# guitar_tuner.net
KiCad netlist of a schematic drawn in EAGLE
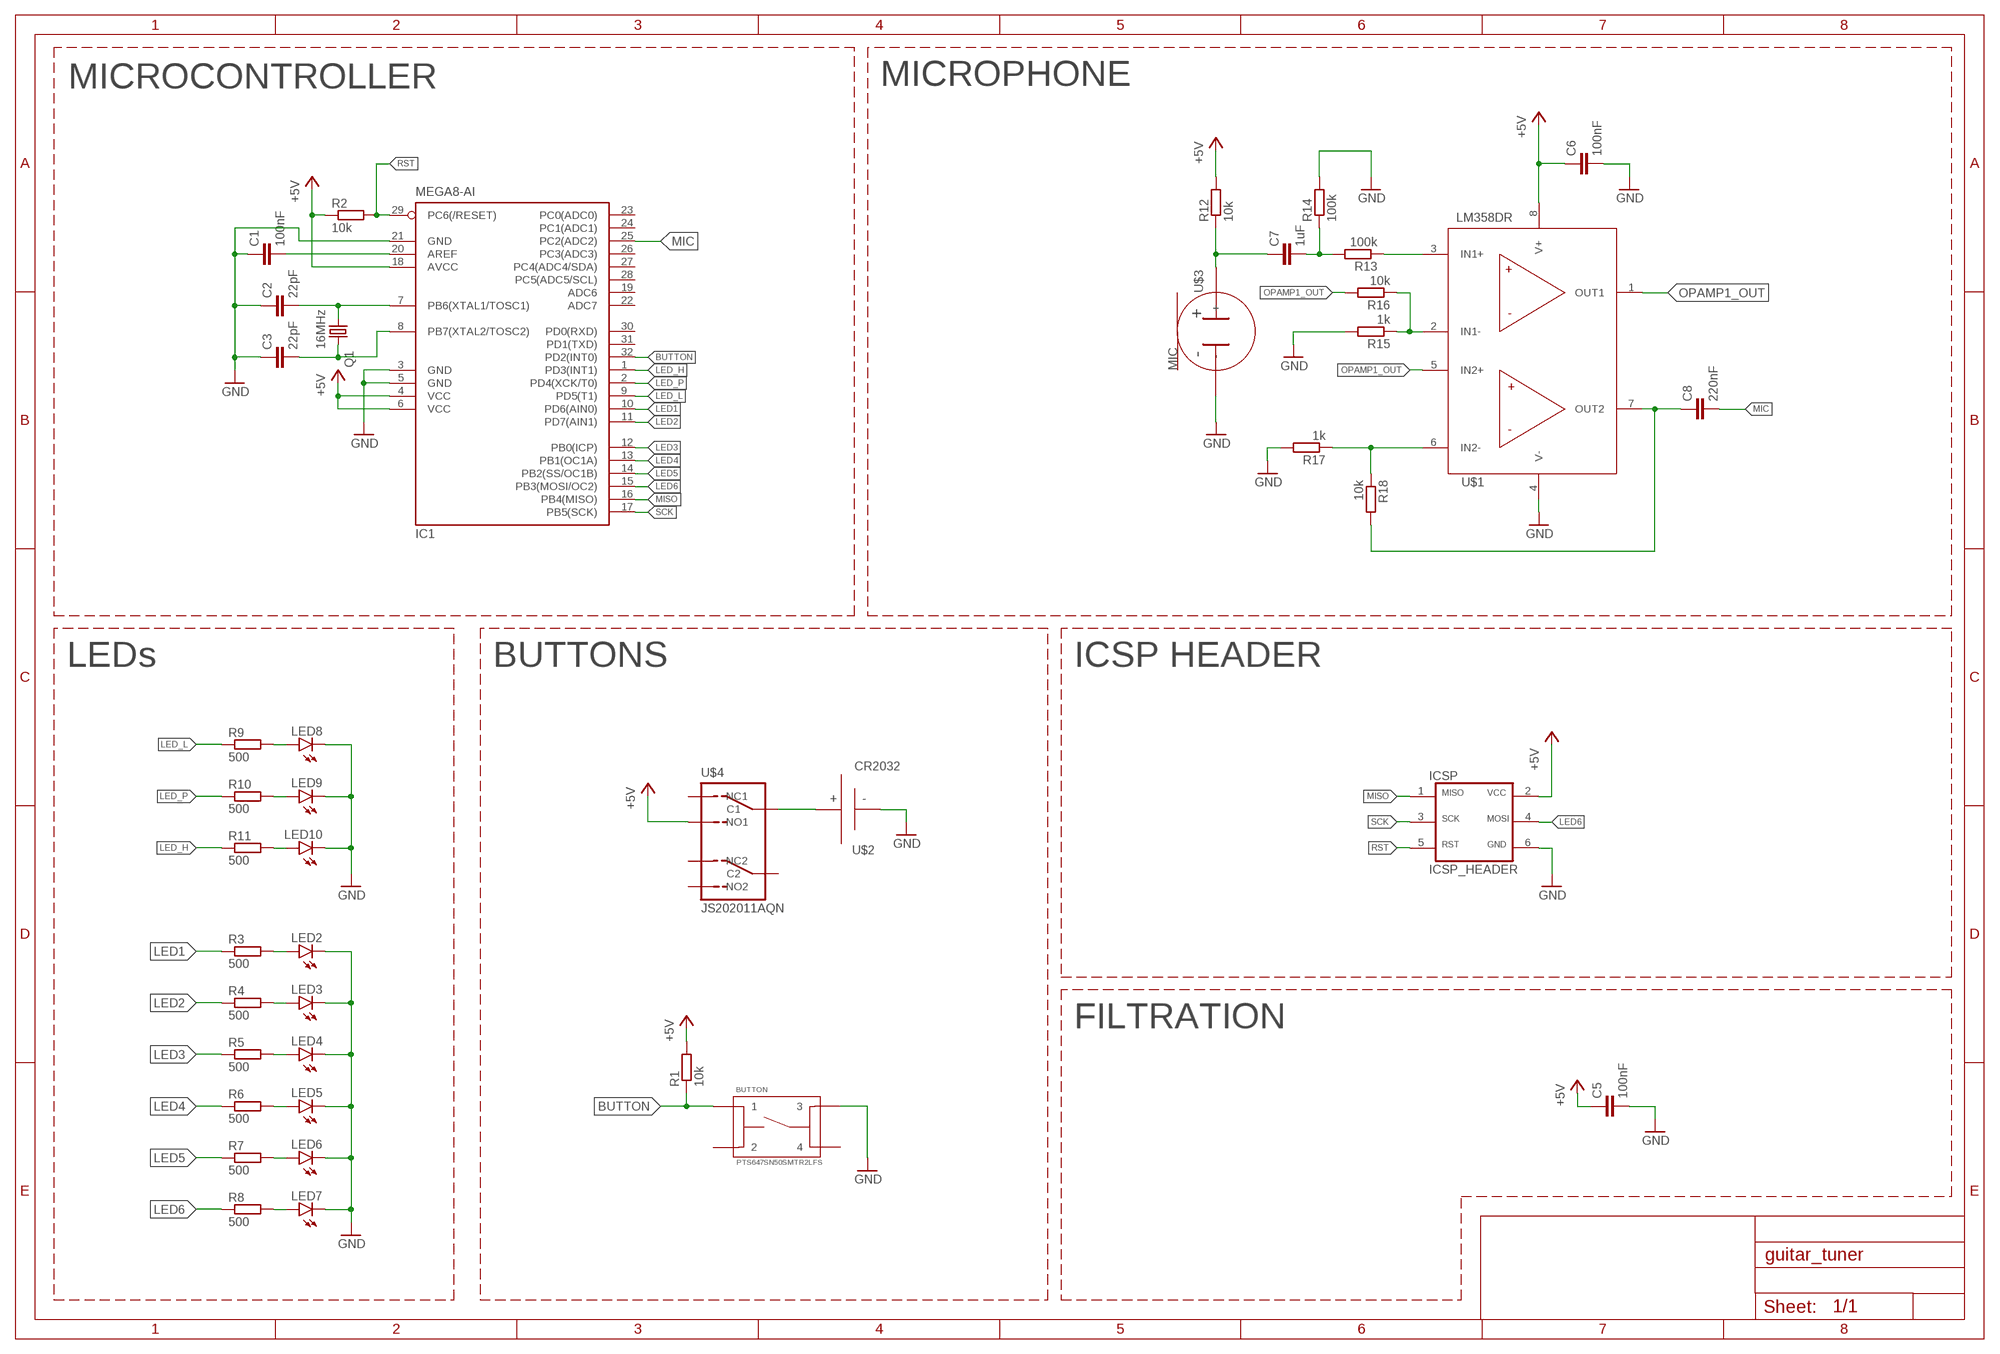
[diagram p0: schematic, sheet 1]

(export (version "E")
  (design (tool "Eeschema 10.0.6"))
  (components
    (comp (ref "BUTTON")
      (value "PTS647SN50SMTR2LFS")
      (footprint "eagle-import:PTS647_SMD_TACTSWITCH")
      (libsource (lib "eagle-import") (part "PTS647SN50SMTR2LFS"))
    )
    (comp (ref "C1")
      (value "100nF")
      (footprint "eagle-import:C0603")
      (libsource (lib "eagle-import") (part "C-EUC0603"))
    )
    (comp (ref "C2")
      (value "22pF")
      (footprint "eagle-import:C0603")
      (libsource (lib "eagle-import") (part "C-EUC0603"))
    )
    (comp (ref "C3")
      (value "22pF")
      (footprint "eagle-import:C0603")
      (libsource (lib "eagle-import") (part "C-EUC0603"))
    )
    (comp (ref "C5")
      (value "100nF")
      (footprint "eagle-import:C0603")
      (libsource (lib "eagle-import") (part "C-EUC0603"))
    )
    (comp (ref "C6")
      (value "100nF")
      (footprint "eagle-import:C0603")
      (libsource (lib "eagle-import") (part "C-EUC0603"))
    )
    (comp (ref "C7")
      (value "1uF")
      (footprint "eagle-import:C0603")
      (libsource (lib "eagle-import") (part "C-EUC0603"))
    )
    (comp (ref "C8")
      (value "220nF")
      (footprint "eagle-import:C0603")
      (libsource (lib "eagle-import") (part "C-EUC0603"))
    )
    (comp (ref "IC1")
      (value "MEGA8-AI")
      (footprint "eagle-import:TQFP32-08")
      (fields (field (name "MPN") "ATMEGA8-16AU"))
      (libsource (lib "eagle-import") (part "MEGA8-AI"))
    )
    (comp (ref "LED2")
      (value "LEDCHIPLED_1206")
      (footprint "eagle-import:CHIPLED_1206")
      (libsource (lib "eagle-import") (part "LEDCHIPLED_1206"))
    )
    (comp (ref "LED3")
      (value "LEDCHIPLED_1206")
      (footprint "eagle-import:CHIPLED_1206")
      (libsource (lib "eagle-import") (part "LEDCHIPLED_1206"))
    )
    (comp (ref "LED4")
      (value "LEDCHIPLED_1206")
      (footprint "eagle-import:CHIPLED_1206")
      (libsource (lib "eagle-import") (part "LEDCHIPLED_1206"))
    )
    (comp (ref "LED5")
      (value "LEDCHIPLED_1206")
      (footprint "eagle-import:CHIPLED_1206")
      (libsource (lib "eagle-import") (part "LEDCHIPLED_1206"))
    )
    (comp (ref "LED6")
      (value "LEDCHIPLED_1206")
      (footprint "eagle-import:CHIPLED_1206")
      (libsource (lib "eagle-import") (part "LEDCHIPLED_1206"))
    )
    (comp (ref "LED7")
      (value "LEDCHIPLED_1206")
      (footprint "eagle-import:CHIPLED_1206")
      (libsource (lib "eagle-import") (part "LEDCHIPLED_1206"))
    )
    (comp (ref "LED8")
      (value "LEDCHIPLED_1206")
      (footprint "eagle-import:CHIPLED_1206")
      (libsource (lib "eagle-import") (part "LEDCHIPLED_1206"))
    )
    (comp (ref "LED9")
      (value "LEDCHIPLED_1206")
      (footprint "eagle-import:CHIPLED_1206")
      (libsource (lib "eagle-import") (part "LEDCHIPLED_1206"))
    )
    (comp (ref "LED10")
      (value "LEDCHIPLED_1206")
      (footprint "eagle-import:CHIPLED_1206")
      (libsource (lib "eagle-import") (part "LEDCHIPLED_1206"))
    )
    (comp (ref "Q1")
      (value "16MHz")
      (footprint "eagle-import:5.0X3.2_2")
      (libsource (lib "eagle-import") (part "KX-9B"))
    )
    (comp (ref "R1")
      (value "10k")
      (footprint "eagle-import:R0603")
      (libsource (lib "eagle-import") (part "R-EU_R0603"))
    )
    (comp (ref "R2")
      (value "10k")
      (footprint "eagle-import:R0603")
      (libsource (lib "eagle-import") (part "R-EU_R0603"))
    )
    (comp (ref "R3")
      (value "500")
      (footprint "eagle-import:R0603")
      (libsource (lib "eagle-import") (part "R-EU_R0603"))
    )
    (comp (ref "R4")
      (value "500")
      (footprint "eagle-import:R0603")
      (libsource (lib "eagle-import") (part "R-EU_R0603"))
    )
    (comp (ref "R5")
      (value "500")
      (footprint "eagle-import:R0603")
      (libsource (lib "eagle-import") (part "R-EU_R0603"))
    )
    (comp (ref "R6")
      (value "500")
      (footprint "eagle-import:R0603")
      (libsource (lib "eagle-import") (part "R-EU_R0603"))
    )
    (comp (ref "R7")
      (value "500")
      (footprint "eagle-import:R0603")
      (libsource (lib "eagle-import") (part "R-EU_R0603"))
    )
    (comp (ref "R8")
      (value "500")
      (footprint "eagle-import:R0603")
      (libsource (lib "eagle-import") (part "R-EU_R0603"))
    )
    (comp (ref "R9")
      (value "500")
      (footprint "eagle-import:R0603")
      (libsource (lib "eagle-import") (part "R-EU_R0603"))
    )
    (comp (ref "R10")
      (value "500")
      (footprint "eagle-import:R0603")
      (libsource (lib "eagle-import") (part "R-EU_R0603"))
    )
    (comp (ref "R11")
      (value "500")
      (footprint "eagle-import:R0603")
      (libsource (lib "eagle-import") (part "R-EU_R0603"))
    )
    (comp (ref "R12")
      (value "10k")
      (footprint "eagle-import:R0603")
      (libsource (lib "eagle-import") (part "R-EU_R0603"))
    )
    (comp (ref "R13")
      (value "100k")
      (footprint "eagle-import:R0603")
      (libsource (lib "eagle-import") (part "R-EU_R0603"))
    )
    (comp (ref "R14")
      (value "100k")
      (footprint "eagle-import:R0603")
      (libsource (lib "eagle-import") (part "R-EU_R0603"))
    )
    (comp (ref "R15")
      (value "1k")
      (footprint "eagle-import:R0603")
      (libsource (lib "eagle-import") (part "R-EU_R0603"))
    )
    (comp (ref "R16")
      (value "10k")
      (footprint "eagle-import:R0603")
      (libsource (lib "eagle-import") (part "R-EU_R0603"))
    )
    (comp (ref "R17")
      (value "1k")
      (footprint "eagle-import:R0603")
      (libsource (lib "eagle-import") (part "R-EU_R0603"))
    )
    (comp (ref "R18")
      (value "10k")
      (footprint "eagle-import:R0603")
      (libsource (lib "eagle-import") (part "R-EU_R0603"))
    )
    (comp (ref "U$1")
      (value "LM358DRLM358DR_SOIC8")
      (footprint "eagle-import:SOIC127P599X175-8N")
      (libsource (lib "eagle-import") (part "LM358DRLM358DR_SOIC8"))
    )
    (comp (ref "U$2")
      (value "BAT-HLD-001-THM")
      (footprint "eagle-import:BAT-HLD-001-THM")
      (libsource (lib "eagle-import") (part "BAT-HLD-001-THM"))
    )
    (comp (ref "U$3")
      (value "CMA-6542PF")
      (footprint "eagle-import:9.7MM_ELECTRET_MICROPHONE")
      (libsource (lib "eagle-import") (part "CMA-6542PF"))
    )
    (comp (ref "U$4")
      (value "JS202011AQN")
      (footprint "eagle-import:JS202011AQN_DPDT")
      (libsource (lib "eagle-import") (part "JS202011AQN"))
    )
    (comp (ref "U$6")
      (value "ICSP_HEADER")
      (footprint "eagle-import:ICSP_HEADER")
      (libsource (lib "eagle-import") (part "ICSP_HEADER"))
    )
  )
  (nets
    (net (code "1") (name "+5V") (class "Default")
      (node (ref "C5") (pin "1") (pinfunction "1_1") (pintype "passive"))
      (node (ref "C6") (pin "1") (pinfunction "1_1") (pintype "passive"))
      (node (ref "IC1") (pin "18") (pinfunction "AVCC_18") (pintype "power_in"))
      (node (ref "IC1") (pin "4") (pinfunction "VCC_4") (pintype "power_in"))
      (node (ref "IC1") (pin "6") (pinfunction "VCC_6") (pintype "power_in"))
      (node (ref "R1") (pin "2") (pinfunction "2_2") (pintype "passive"))
      (node (ref "R12") (pin "2") (pinfunction "2_2") (pintype "passive"))
      (node (ref "R2") (pin "1") (pinfunction "1_1") (pintype "passive"))
      (node (ref "U$1") (pin "8") (pinfunction "V+_8") (pintype "bidirectional"))
      (node (ref "U$4") (pin "P$2") (pinfunction "NO1_P$2") (pintype "bidirectional"))
      (node (ref "U$6") (pin "2") (pinfunction "VCC_2") (pintype "passive"))
    )
    (net (code "2") (name "BUTTON") (class "Default")
      (node (ref "BUTTON") (pin "P$1") (pinfunction "1_P$1") (pintype "bidirectional"))
      (node (ref "IC1") (pin "32") (pinfunction "PD2(INT0)_32") (pintype "bidirectional"))
      (node (ref "R1") (pin "1") (pinfunction "1_1") (pintype "passive"))
    )
    (net (code "3") (name "GND") (class "Default")
      (node (ref "BUTTON") (pin "P$2") (pinfunction "3_P$2") (pintype "bidirectional"))
      (node (ref "C1") (pin "1") (pinfunction "1_1") (pintype "passive"))
      (node (ref "C2") (pin "1") (pinfunction "1_1") (pintype "passive"))
      (node (ref "C3") (pin "1") (pinfunction "1_1") (pintype "passive"))
      (node (ref "C5") (pin "2") (pinfunction "2_2") (pintype "passive"))
      (node (ref "C6") (pin "2") (pinfunction "2_2") (pintype "passive"))
      (node (ref "IC1") (pin "21") (pinfunction "GND_21") (pintype "power_in"))
      (node (ref "IC1") (pin "3") (pinfunction "GND_3") (pintype "power_in"))
      (node (ref "IC1") (pin "5") (pinfunction "GND_5") (pintype "power_in"))
      (node (ref "LED10") (pin "C") (pinfunction "C_C") (pintype "passive"))
      (node (ref "LED2") (pin "C") (pinfunction "C_C") (pintype "passive"))
      (node (ref "LED3") (pin "C") (pinfunction "C_C") (pintype "passive"))
      (node (ref "LED4") (pin "C") (pinfunction "C_C") (pintype "passive"))
      (node (ref "LED5") (pin "C") (pinfunction "C_C") (pintype "passive"))
      (node (ref "LED6") (pin "C") (pinfunction "C_C") (pintype "passive"))
      (node (ref "LED7") (pin "C") (pinfunction "C_C") (pintype "passive"))
      (node (ref "LED8") (pin "C") (pinfunction "C_C") (pintype "passive"))
      (node (ref "LED9") (pin "C") (pinfunction "C_C") (pintype "passive"))
      (node (ref "R14") (pin "2") (pinfunction "2_2") (pintype "passive"))
      (node (ref "R15") (pin "2") (pinfunction "2_2") (pintype "passive"))
      (node (ref "R17") (pin "2") (pinfunction "2_2") (pintype "passive"))
      (node (ref "U$1") (pin "4") (pinfunction "V-_4") (pintype "bidirectional"))
      (node (ref "U$2") (pin "P$6") (pinfunction "GND_P$6") (pintype "bidirectional"))
      (node (ref "U$3") (pin "P$2") (pinfunction "-_P$2") (pintype "bidirectional"))
      (node (ref "U$6") (pin "6") (pinfunction "GND_6") (pintype "passive"))
    )
    (net (code "4") (name "LED1") (class "Default")
      (node (ref "IC1") (pin "10") (pinfunction "PD6(AIN0)_10") (pintype "bidirectional"))
      (node (ref "R3") (pin "1") (pinfunction "1_1") (pintype "passive"))
    )
    (net (code "5") (name "LED2") (class "Default")
      (node (ref "IC1") (pin "11") (pinfunction "PD7(AIN1)_11") (pintype "bidirectional"))
      (node (ref "R4") (pin "1") (pinfunction "1_1") (pintype "passive"))
    )
    (net (code "6") (name "LED3") (class "Default")
      (node (ref "IC1") (pin "12") (pinfunction "PB0(ICP)_12") (pintype "bidirectional"))
      (node (ref "R5") (pin "1") (pinfunction "1_1") (pintype "passive"))
    )
    (net (code "7") (name "LED4") (class "Default")
      (node (ref "IC1") (pin "13") (pinfunction "PB1(OC1A)_13") (pintype "bidirectional"))
      (node (ref "R6") (pin "1") (pinfunction "1_1") (pintype "passive"))
    )
    (net (code "8") (name "LED5") (class "Default")
      (node (ref "IC1") (pin "14") (pinfunction "PB2(SS/OC1B)_14") (pintype "bidirectional"))
      (node (ref "R7") (pin "1") (pinfunction "1_1") (pintype "passive"))
    )
    (net (code "9") (name "LED6") (class "Default")
      (node (ref "IC1") (pin "15") (pinfunction "PB3(MOSI/OC2)_15") (pintype "bidirectional"))
      (node (ref "R8") (pin "1") (pinfunction "1_1") (pintype "passive"))
      (node (ref "U$6") (pin "4") (pinfunction "MOSI_4") (pintype "passive"))
    )
    (net (code "10") (name "LED_H") (class "Default")
      (node (ref "IC1") (pin "1") (pinfunction "PD3(INT1)_1") (pintype "bidirectional"))
      (node (ref "R11") (pin "1") (pinfunction "1_1") (pintype "passive"))
    )
    (net (code "11") (name "LED_L") (class "Default")
      (node (ref "IC1") (pin "9") (pinfunction "PD5(T1)_9") (pintype "bidirectional"))
      (node (ref "R9") (pin "1") (pinfunction "1_1") (pintype "passive"))
    )
    (net (code "12") (name "LED_P") (class "Default")
      (node (ref "IC1") (pin "2") (pinfunction "PD4(XCK/T0)_2") (pintype "bidirectional"))
      (node (ref "R10") (pin "1") (pinfunction "1_1") (pintype "passive"))
    )
    (net (code "13") (name "MIC") (class "Default")
      (node (ref "C8") (pin "2") (pinfunction "2_2") (pintype "passive"))
      (node (ref "IC1") (pin "25") (pinfunction "PC2(ADC2)_25") (pintype "bidirectional"))
    )
    (net (code "14") (name "MISO") (class "Default")
      (node (ref "IC1") (pin "16") (pinfunction "PB4(MISO)_16") (pintype "bidirectional"))
      (node (ref "U$6") (pin "1") (pinfunction "MISO_1") (pintype "passive"))
    )
    (net (code "15") (name "Net-(C7-Pad2)") (class "Default")
      (node (ref "C7") (pin "2") (pinfunction "2_2") (pintype "passive"))
      (node (ref "R13") (pin "2") (pinfunction "2_2") (pintype "passive"))
      (node (ref "R14") (pin "1") (pinfunction "1_1") (pintype "passive"))
    )
    (net (code "16") (name "Net-(IC1-AREF)") (class "Default")
      (node (ref "C1") (pin "2") (pinfunction "2_2") (pintype "passive"))
      (node (ref "IC1") (pin "20") (pinfunction "AREF_20") (pintype "passive"))
    )
    (net (code "17") (name "Net-(IC1-PB6(XTAL1{slash}TOSC1))") (class "Default")
      (node (ref "C2") (pin "2") (pinfunction "2_2") (pintype "passive"))
      (node (ref "IC1") (pin "7") (pinfunction "PB6(XTAL1/TOSC1)_7") (pintype "bidirectional"))
      (node (ref "Q1") (pin "1") (pinfunction "1_1") (pintype "passive"))
    )
    (net (code "18") (name "Net-(IC1-PB7(XTAL2{slash}TOSC2))") (class "Default")
      (node (ref "C3") (pin "2") (pinfunction "2_2") (pintype "passive"))
      (node (ref "IC1") (pin "8") (pinfunction "PB7(XTAL2/TOSC2)_8") (pintype "bidirectional"))
      (node (ref "Q1") (pin "2") (pinfunction "2_2") (pintype "passive"))
    )
    (net (code "19") (name "Net-(LED2-PadA)") (class "Default")
      (node (ref "LED2") (pin "A") (pinfunction "A_A") (pintype "passive"))
      (node (ref "R3") (pin "2") (pinfunction "2_2") (pintype "passive"))
    )
    (net (code "20") (name "Net-(LED3-PadA)") (class "Default")
      (node (ref "LED3") (pin "A") (pinfunction "A_A") (pintype "passive"))
      (node (ref "R4") (pin "2") (pinfunction "2_2") (pintype "passive"))
    )
    (net (code "21") (name "Net-(LED4-PadA)") (class "Default")
      (node (ref "LED4") (pin "A") (pinfunction "A_A") (pintype "passive"))
      (node (ref "R5") (pin "2") (pinfunction "2_2") (pintype "passive"))
    )
    (net (code "22") (name "Net-(LED5-PadA)") (class "Default")
      (node (ref "LED5") (pin "A") (pinfunction "A_A") (pintype "passive"))
      (node (ref "R6") (pin "2") (pinfunction "2_2") (pintype "passive"))
    )
    (net (code "23") (name "Net-(LED6-PadA)") (class "Default")
      (node (ref "LED6") (pin "A") (pinfunction "A_A") (pintype "passive"))
      (node (ref "R7") (pin "2") (pinfunction "2_2") (pintype "passive"))
    )
    (net (code "24") (name "Net-(LED7-PadA)") (class "Default")
      (node (ref "LED7") (pin "A") (pinfunction "A_A") (pintype "passive"))
      (node (ref "R8") (pin "2") (pinfunction "2_2") (pintype "passive"))
    )
    (net (code "25") (name "Net-(LED8-PadA)") (class "Default")
      (node (ref "LED8") (pin "A") (pinfunction "A_A") (pintype "passive"))
      (node (ref "R9") (pin "2") (pinfunction "2_2") (pintype "passive"))
    )
    (net (code "26") (name "Net-(LED9-PadA)") (class "Default")
      (node (ref "LED9") (pin "A") (pinfunction "A_A") (pintype "passive"))
      (node (ref "R10") (pin "2") (pinfunction "2_2") (pintype "passive"))
    )
    (net (code "27") (name "Net-(LED10-PadA)") (class "Default")
      (node (ref "LED10") (pin "A") (pinfunction "A_A") (pintype "passive"))
      (node (ref "R11") (pin "2") (pinfunction "2_2") (pintype "passive"))
    )
    (net (code "28") (name "Net-(U$1-IN1+)") (class "Default")
      (node (ref "R13") (pin "1") (pinfunction "1_1") (pintype "passive"))
      (node (ref "U$1") (pin "3") (pinfunction "IN1+_3") (pintype "bidirectional"))
    )
    (net (code "29") (name "Net-(U$1-IN1-)") (class "Default")
      (node (ref "R15") (pin "1") (pinfunction "1_1") (pintype "passive"))
      (node (ref "R16") (pin "1") (pinfunction "1_1") (pintype "passive"))
      (node (ref "U$1") (pin "2") (pinfunction "IN1-_2") (pintype "bidirectional"))
    )
    (net (code "30") (name "Net-(U$1-IN2-)") (class "Default")
      (node (ref "R17") (pin "1") (pinfunction "1_1") (pintype "passive"))
      (node (ref "R18") (pin "1") (pinfunction "1_1") (pintype "passive"))
      (node (ref "U$1") (pin "6") (pinfunction "IN2-_6") (pintype "bidirectional"))
    )
    (net (code "31") (name "Net-(U$1-OUT2)") (class "Default")
      (node (ref "C8") (pin "1") (pinfunction "1_1") (pintype "passive"))
      (node (ref "R18") (pin "2") (pinfunction "2_2") (pintype "passive"))
      (node (ref "U$1") (pin "7") (pinfunction "OUT2_7") (pintype "bidirectional"))
    )
    (net (code "32") (name "Net-(U$3-+)") (class "Default")
      (node (ref "C7") (pin "1") (pinfunction "1_1") (pintype "passive"))
      (node (ref "R12") (pin "1") (pinfunction "1_1") (pintype "passive"))
      (node (ref "U$3") (pin "P$1") (pinfunction "+_P$1") (pintype "bidirectional"))
    )
    (net (code "33") (name "Net-(U$4-C1)") (class "Default")
      (node (ref "U$2") (pin "P$1") (pinfunction "5V_P$1") (pintype "bidirectional"))
      (node (ref "U$2") (pin "P$2") (pinfunction "5V_P$2") (pintype "bidirectional"))
      (node (ref "U$2") (pin "P$3") (pinfunction "5V_P$3") (pintype "bidirectional"))
      (node (ref "U$2") (pin "P$4") (pinfunction "5V_P$4") (pintype "bidirectional"))
      (node (ref "U$2") (pin "P$5") (pinfunction "5V_P$5") (pintype "bidirectional"))
      (node (ref "U$4") (pin "P$3") (pinfunction "C1_P$3") (pintype "bidirectional"))
    )
    (net (code "34") (name "OPAMP1_OUT") (class "Default")
      (node (ref "R16") (pin "2") (pinfunction "2_2") (pintype "passive"))
      (node (ref "U$1") (pin "1") (pinfunction "OUT1_1") (pintype "bidirectional"))
      (node (ref "U$1") (pin "5") (pinfunction "IN2+_5") (pintype "bidirectional"))
    )
    (net (code "35") (name "RST") (class "Default")
      (node (ref "IC1") (pin "29") (pinfunction "PC6(/RESET)_29") (pintype "bidirectional"))
      (node (ref "R2") (pin "2") (pinfunction "2_2") (pintype "passive"))
      (node (ref "U$6") (pin "5") (pinfunction "RST_5") (pintype "passive"))
    )
    (net (code "36") (name "SCK") (class "Default")
      (node (ref "IC1") (pin "17") (pinfunction "PB5(SCK)_17") (pintype "bidirectional"))
      (node (ref "U$6") (pin "3") (pinfunction "SCK_3") (pintype "passive"))
    )
    (net (code "37") (name "unconnected-(BUTTON-2-PadP$3)") (class "Default")
      (node (ref "BUTTON") (pin "P$3") (pinfunction "2_P$3") (pintype "bidirectional"))
    )
    (net (code "38") (name "unconnected-(BUTTON-4-PadP$4)") (class "Default")
      (node (ref "BUTTON") (pin "P$4") (pinfunction "4_P$4") (pintype "bidirectional"))
    )
    (net (code "39") (name "unconnected-(IC1-ADC6-Pad19)") (class "Default")
      (node (ref "IC1") (pin "19") (pinfunction "ADC6_19") (pintype "bidirectional"))
    )
    (net (code "40") (name "unconnected-(IC1-ADC7-Pad22)") (class "Default")
      (node (ref "IC1") (pin "22") (pinfunction "ADC7_22") (pintype "bidirectional"))
    )
    (net (code "41") (name "unconnected-(IC1-PC0(ADC0)-Pad23)") (class "Default")
      (node (ref "IC1") (pin "23") (pinfunction "PC0(ADC0)_23") (pintype "bidirectional"))
    )
    (net (code "42") (name "unconnected-(IC1-PC1(ADC1)-Pad24)") (class "Default")
      (node (ref "IC1") (pin "24") (pinfunction "PC1(ADC1)_24") (pintype "bidirectional"))
    )
    (net (code "43") (name "unconnected-(IC1-PC3(ADC3)-Pad26)") (class "Default")
      (node (ref "IC1") (pin "26") (pinfunction "PC3(ADC3)_26") (pintype "bidirectional"))
    )
    (net (code "44") (name "unconnected-(IC1-PC4(ADC4{slash}SDA)-Pad27)") (class "Default")
      (node (ref "IC1") (pin "27") (pinfunction "PC4(ADC4/SDA)_27") (pintype "bidirectional"))
    )
    (net (code "45") (name "unconnected-(IC1-PC5(ADC5{slash}SCL)-Pad28)") (class "Default")
      (node (ref "IC1") (pin "28") (pinfunction "PC5(ADC5/SCL)_28") (pintype "bidirectional"))
    )
    (net (code "46") (name "unconnected-(IC1-PD0(RXD)-Pad30)") (class "Default")
      (node (ref "IC1") (pin "30") (pinfunction "PD0(RXD)_30") (pintype "bidirectional"))
    )
    (net (code "47") (name "unconnected-(IC1-PD1(TXD)-Pad31)") (class "Default")
      (node (ref "IC1") (pin "31") (pinfunction "PD1(TXD)_31") (pintype "bidirectional"))
    )
    (net (code "48") (name "unconnected-(U$4-C2-PadP$4)") (class "Default")
      (node (ref "U$4") (pin "P$4") (pinfunction "C2_P$4") (pintype "bidirectional"))
    )
    (net (code "49") (name "unconnected-(U$4-NC1-PadP$6)") (class "Default")
      (node (ref "U$4") (pin "P$6") (pinfunction "NC1_P$6") (pintype "bidirectional"))
    )
    (net (code "50") (name "unconnected-(U$4-NC2-PadP$5)") (class "Default")
      (node (ref "U$4") (pin "P$5") (pinfunction "NC2_P$5") (pintype "bidirectional"))
    )
    (net (code "51") (name "unconnected-(U$4-NO2-PadP$1)") (class "Default")
      (node (ref "U$4") (pin "P$1") (pinfunction "NO2_P$1") (pintype "bidirectional"))
    )
  )
)
